# LEDMotherboard.net
KiCad netlist of a schematic drawn in EAGLE
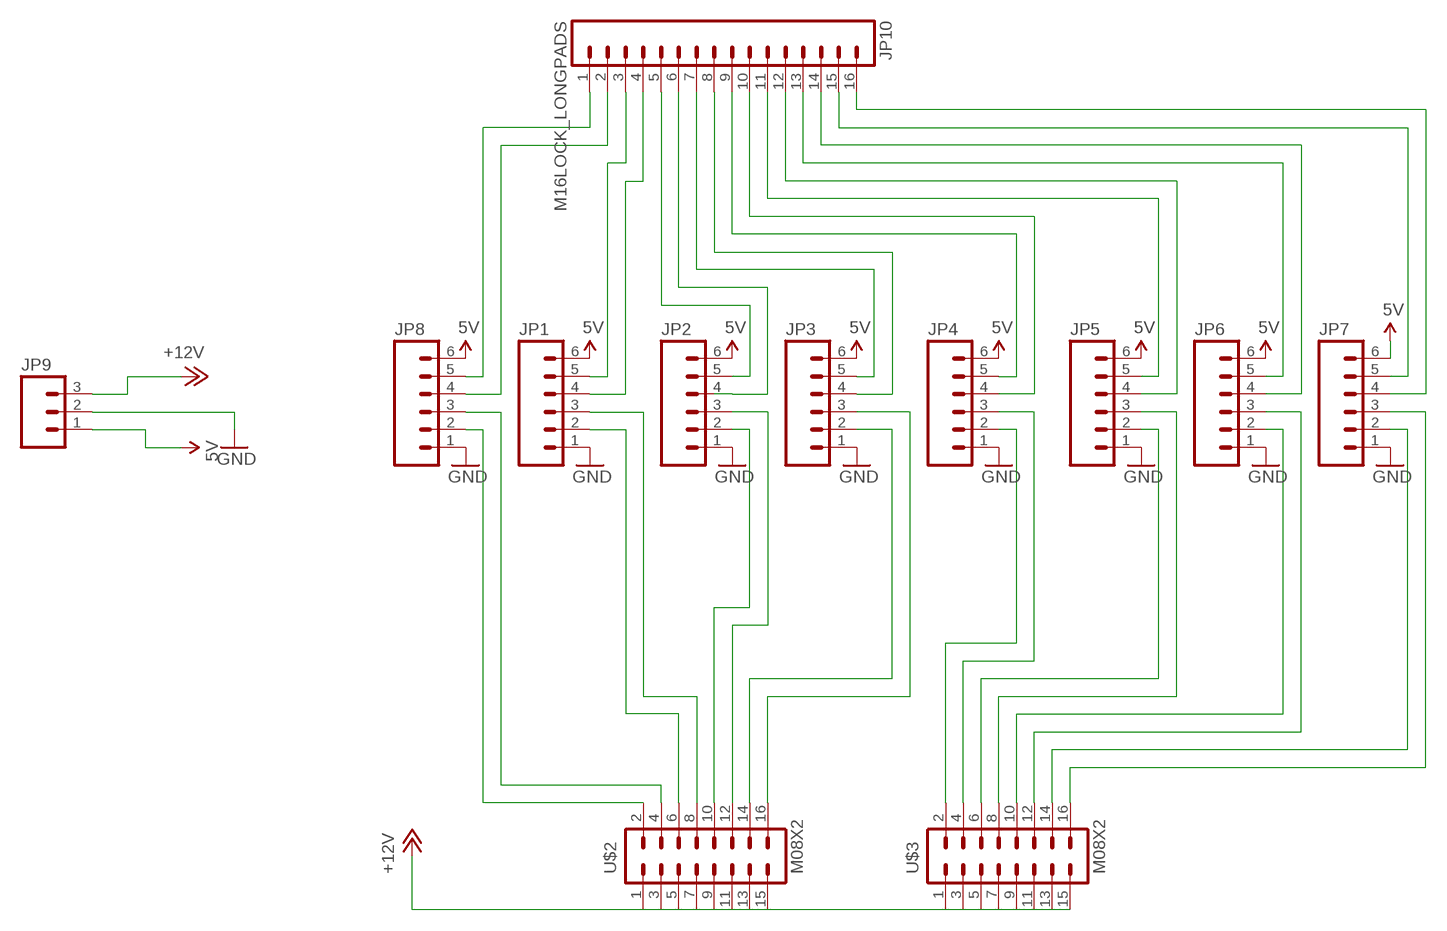
[diagram p0: schematic, sheet 1]

(export (version "E")
  (design (tool "Eeschema 10.0.6"))
  (components
    (comp (ref "JP1")
      (value "M06LOCK_LONGPADS")
      (footprint "eagle-import:1X06_LOCK_LONGPADS")
      (libsource (lib "eagle-import") (part "M06LOCK_LONGPADS"))
    )
    (comp (ref "JP2")
      (value "M06LOCK_LONGPADS")
      (footprint "eagle-import:1X06_LOCK_LONGPADS")
      (libsource (lib "eagle-import") (part "M06LOCK_LONGPADS"))
    )
    (comp (ref "JP3")
      (value "M06LOCK_LONGPADS")
      (footprint "eagle-import:1X06_LOCK_LONGPADS")
      (libsource (lib "eagle-import") (part "M06LOCK_LONGPADS"))
    )
    (comp (ref "JP4")
      (value "M06LOCK_LONGPADS")
      (footprint "eagle-import:1X06_LOCK_LONGPADS")
      (libsource (lib "eagle-import") (part "M06LOCK_LONGPADS"))
    )
    (comp (ref "JP5")
      (value "M06LOCK_LONGPADS")
      (footprint "eagle-import:1X06_LOCK_LONGPADS")
      (libsource (lib "eagle-import") (part "M06LOCK_LONGPADS"))
    )
    (comp (ref "JP6")
      (value "M06LOCK_LONGPADS")
      (footprint "eagle-import:1X06_LOCK_LONGPADS")
      (libsource (lib "eagle-import") (part "M06LOCK_LONGPADS"))
    )
    (comp (ref "JP7")
      (value "M06LOCK_LONGPADS")
      (footprint "eagle-import:1X06_LOCK_LONGPADS")
      (libsource (lib "eagle-import") (part "M06LOCK_LONGPADS"))
    )
    (comp (ref "JP8")
      (value "M06LOCK_LONGPADS")
      (footprint "eagle-import:1X06_LOCK_LONGPADS")
      (libsource (lib "eagle-import") (part "M06LOCK_LONGPADS"))
    )
    (comp (ref "JP9")
      (value "M03-SCREW-5MM")
      (footprint "eagle-import:SCREWTERMINAL-5MM-3")
      (libsource (lib "eagle-import") (part "M03-SCREW-5MM"))
    )
    (comp (ref "JP10")
      (value "M16LOCK_LONGPADS")
      (footprint "eagle-import:1X16_LOCK_LONGPADS")
      (libsource (lib "eagle-import") (part "M16LOCK_LONGPADS"))
    )
    (comp (ref "U$2")
      (value "M08X2")
      (footprint "eagle-import:2X8")
      (libsource (lib "eagle-import") (part "M08X2"))
    )
    (comp (ref "U$3")
      (value "M08X2")
      (footprint "eagle-import:2X8")
      (libsource (lib "eagle-import") (part "M08X2"))
    )
  )
  (nets
    (net (code "1") (name "+12V") (class "Default")
      (node (ref "JP9") (pin "3") (pinfunction "3_3") (pintype "passive"))
      (node (ref "U$2") (pin "1") (pinfunction "1_1") (pintype "passive"))
      (node (ref "U$2") (pin "11") (pinfunction "11_11") (pintype "passive"))
      (node (ref "U$2") (pin "13") (pinfunction "13_13") (pintype "passive"))
      (node (ref "U$2") (pin "15") (pinfunction "15_15") (pintype "passive"))
      (node (ref "U$2") (pin "3") (pinfunction "3_3") (pintype "passive"))
      (node (ref "U$2") (pin "5") (pinfunction "5_5") (pintype "passive"))
      (node (ref "U$2") (pin "7") (pinfunction "7_7") (pintype "passive"))
      (node (ref "U$2") (pin "9") (pinfunction "9_9") (pintype "passive"))
      (node (ref "U$3") (pin "1") (pinfunction "1_1") (pintype "passive"))
      (node (ref "U$3") (pin "11") (pinfunction "11_11") (pintype "passive"))
      (node (ref "U$3") (pin "13") (pinfunction "13_13") (pintype "passive"))
      (node (ref "U$3") (pin "15") (pinfunction "15_15") (pintype "passive"))
      (node (ref "U$3") (pin "3") (pinfunction "3_3") (pintype "passive"))
      (node (ref "U$3") (pin "5") (pinfunction "5_5") (pintype "passive"))
      (node (ref "U$3") (pin "7") (pinfunction "7_7") (pintype "passive"))
      (node (ref "U$3") (pin "9") (pinfunction "9_9") (pintype "passive"))
    )
    (net (code "2") (name "5V") (class "Default")
      (node (ref "JP1") (pin "6") (pinfunction "6_6") (pintype "passive"))
      (node (ref "JP2") (pin "6") (pinfunction "6_6") (pintype "passive"))
      (node (ref "JP3") (pin "6") (pinfunction "6_6") (pintype "passive"))
      (node (ref "JP4") (pin "6") (pinfunction "6_6") (pintype "passive"))
      (node (ref "JP5") (pin "6") (pinfunction "6_6") (pintype "passive"))
      (node (ref "JP6") (pin "6") (pinfunction "6_6") (pintype "passive"))
      (node (ref "JP7") (pin "6") (pinfunction "6_6") (pintype "passive"))
      (node (ref "JP8") (pin "6") (pinfunction "6_6") (pintype "passive"))
      (node (ref "JP9") (pin "1") (pinfunction "1_1") (pintype "passive"))
    )
    (net (code "3") (name "GND") (class "Default")
      (node (ref "JP1") (pin "1") (pinfunction "1_1") (pintype "passive"))
      (node (ref "JP2") (pin "1") (pinfunction "1_1") (pintype "passive"))
      (node (ref "JP3") (pin "1") (pinfunction "1_1") (pintype "passive"))
      (node (ref "JP4") (pin "1") (pinfunction "1_1") (pintype "passive"))
      (node (ref "JP5") (pin "1") (pinfunction "1_1") (pintype "passive"))
      (node (ref "JP6") (pin "1") (pinfunction "1_1") (pintype "passive"))
      (node (ref "JP7") (pin "1") (pinfunction "1_1") (pintype "passive"))
      (node (ref "JP8") (pin "1") (pinfunction "1_1") (pintype "passive"))
      (node (ref "JP9") (pin "2") (pinfunction "2_2") (pintype "passive"))
    )
    (net (code "4") (name "Net-(JP1-Pad2)") (class "Default")
      (node (ref "JP1") (pin "2") (pinfunction "2_2") (pintype "passive"))
      (node (ref "U$2") (pin "6") (pinfunction "6_6") (pintype "passive"))
    )
    (net (code "5") (name "Net-(JP1-Pad3)") (class "Default")
      (node (ref "JP1") (pin "3") (pinfunction "3_3") (pintype "passive"))
      (node (ref "U$2") (pin "8") (pinfunction "8_8") (pintype "passive"))
    )
    (net (code "6") (name "Net-(JP1-Pad4)") (class "Default")
      (node (ref "JP1") (pin "4") (pinfunction "4_4") (pintype "passive"))
      (node (ref "JP10") (pin "4") (pinfunction "4_4") (pintype "passive"))
    )
    (net (code "7") (name "Net-(JP1-Pad5)") (class "Default")
      (node (ref "JP1") (pin "5") (pinfunction "5_5") (pintype "passive"))
      (node (ref "JP10") (pin "3") (pinfunction "3_3") (pintype "passive"))
    )
    (net (code "8") (name "Net-(JP2-Pad2)") (class "Default")
      (node (ref "JP2") (pin "2") (pinfunction "2_2") (pintype "passive"))
      (node (ref "U$2") (pin "10") (pinfunction "10_10") (pintype "passive"))
    )
    (net (code "9") (name "Net-(JP2-Pad3)") (class "Default")
      (node (ref "JP2") (pin "3") (pinfunction "3_3") (pintype "passive"))
      (node (ref "U$2") (pin "12") (pinfunction "12_12") (pintype "passive"))
    )
    (net (code "10") (name "Net-(JP3-Pad2)") (class "Default")
      (node (ref "JP3") (pin "2") (pinfunction "2_2") (pintype "passive"))
      (node (ref "U$2") (pin "14") (pinfunction "14_14") (pintype "passive"))
    )
    (net (code "11") (name "Net-(JP3-Pad3)") (class "Default")
      (node (ref "JP3") (pin "3") (pinfunction "3_3") (pintype "passive"))
      (node (ref "U$2") (pin "16") (pinfunction "16_16") (pintype "passive"))
    )
    (net (code "12") (name "Net-(JP4-Pad2)") (class "Default")
      (node (ref "JP4") (pin "2") (pinfunction "2_2") (pintype "passive"))
      (node (ref "U$3") (pin "2") (pinfunction "2_2") (pintype "passive"))
    )
    (net (code "13") (name "Net-(JP4-Pad3)") (class "Default")
      (node (ref "JP4") (pin "3") (pinfunction "3_3") (pintype "passive"))
      (node (ref "U$3") (pin "4") (pinfunction "4_4") (pintype "passive"))
    )
    (net (code "14") (name "Net-(JP5-Pad2)") (class "Default")
      (node (ref "JP5") (pin "2") (pinfunction "2_2") (pintype "passive"))
      (node (ref "U$3") (pin "6") (pinfunction "6_6") (pintype "passive"))
    )
    (net (code "15") (name "Net-(JP5-Pad3)") (class "Default")
      (node (ref "JP5") (pin "3") (pinfunction "3_3") (pintype "passive"))
      (node (ref "U$3") (pin "8") (pinfunction "8_8") (pintype "passive"))
    )
    (net (code "16") (name "Net-(JP6-Pad2)") (class "Default")
      (node (ref "JP6") (pin "2") (pinfunction "2_2") (pintype "passive"))
      (node (ref "U$3") (pin "10") (pinfunction "10_10") (pintype "passive"))
    )
    (net (code "17") (name "Net-(JP6-Pad3)") (class "Default")
      (node (ref "JP6") (pin "3") (pinfunction "3_3") (pintype "passive"))
      (node (ref "U$3") (pin "12") (pinfunction "12_12") (pintype "passive"))
    )
    (net (code "18") (name "Net-(JP7-Pad2)") (class "Default")
      (node (ref "JP7") (pin "2") (pinfunction "2_2") (pintype "passive"))
      (node (ref "U$3") (pin "14") (pinfunction "14_14") (pintype "passive"))
    )
    (net (code "19") (name "Net-(JP7-Pad3)") (class "Default")
      (node (ref "JP7") (pin "3") (pinfunction "3_3") (pintype "passive"))
      (node (ref "U$3") (pin "16") (pinfunction "16_16") (pintype "passive"))
    )
    (net (code "20") (name "Net-(JP8-Pad2)") (class "Default")
      (node (ref "JP8") (pin "2") (pinfunction "2_2") (pintype "passive"))
      (node (ref "U$2") (pin "2") (pinfunction "2_2") (pintype "passive"))
    )
    (net (code "21") (name "Net-(JP8-Pad3)") (class "Default")
      (node (ref "JP8") (pin "3") (pinfunction "3_3") (pintype "passive"))
      (node (ref "U$2") (pin "4") (pinfunction "4_4") (pintype "passive"))
    )
    (net (code "22") (name "Net-(JP10-Pad1)") (class "Default")
      (node (ref "JP10") (pin "1") (pinfunction "1_1") (pintype "passive"))
      (node (ref "JP8") (pin "5") (pinfunction "5_5") (pintype "passive"))
    )
    (net (code "23") (name "Net-(JP10-Pad2)") (class "Default")
      (node (ref "JP10") (pin "2") (pinfunction "2_2") (pintype "passive"))
      (node (ref "JP8") (pin "4") (pinfunction "4_4") (pintype "passive"))
    )
    (net (code "24") (name "Net-(JP10-Pad5)") (class "Default")
      (node (ref "JP10") (pin "5") (pinfunction "5_5") (pintype "passive"))
      (node (ref "JP2") (pin "5") (pinfunction "5_5") (pintype "passive"))
    )
    (net (code "25") (name "Net-(JP10-Pad6)") (class "Default")
      (node (ref "JP10") (pin "6") (pinfunction "6_6") (pintype "passive"))
      (node (ref "JP2") (pin "4") (pinfunction "4_4") (pintype "passive"))
    )
    (net (code "26") (name "Net-(JP10-Pad7)") (class "Default")
      (node (ref "JP10") (pin "7") (pinfunction "7_7") (pintype "passive"))
      (node (ref "JP3") (pin "5") (pinfunction "5_5") (pintype "passive"))
    )
    (net (code "27") (name "Net-(JP10-Pad8)") (class "Default")
      (node (ref "JP10") (pin "8") (pinfunction "8_8") (pintype "passive"))
      (node (ref "JP3") (pin "4") (pinfunction "4_4") (pintype "passive"))
    )
    (net (code "28") (name "Net-(JP10-Pad9)") (class "Default")
      (node (ref "JP10") (pin "9") (pinfunction "9_9") (pintype "passive"))
      (node (ref "JP4") (pin "5") (pinfunction "5_5") (pintype "passive"))
    )
    (net (code "29") (name "Net-(JP10-Pad10)") (class "Default")
      (node (ref "JP10") (pin "10") (pinfunction "10_10") (pintype "passive"))
      (node (ref "JP4") (pin "4") (pinfunction "4_4") (pintype "passive"))
    )
    (net (code "30") (name "Net-(JP10-Pad11)") (class "Default")
      (node (ref "JP10") (pin "11") (pinfunction "11_11") (pintype "passive"))
      (node (ref "JP5") (pin "5") (pinfunction "5_5") (pintype "passive"))
    )
    (net (code "31") (name "Net-(JP10-Pad12)") (class "Default")
      (node (ref "JP10") (pin "12") (pinfunction "12_12") (pintype "passive"))
      (node (ref "JP5") (pin "4") (pinfunction "4_4") (pintype "passive"))
    )
    (net (code "32") (name "Net-(JP10-Pad13)") (class "Default")
      (node (ref "JP10") (pin "13") (pinfunction "13_13") (pintype "passive"))
      (node (ref "JP6") (pin "5") (pinfunction "5_5") (pintype "passive"))
    )
    (net (code "33") (name "Net-(JP10-Pad14)") (class "Default")
      (node (ref "JP10") (pin "14") (pinfunction "14_14") (pintype "passive"))
      (node (ref "JP6") (pin "4") (pinfunction "4_4") (pintype "passive"))
    )
    (net (code "34") (name "Net-(JP10-Pad15)") (class "Default")
      (node (ref "JP10") (pin "15") (pinfunction "15_15") (pintype "passive"))
      (node (ref "JP7") (pin "5") (pinfunction "5_5") (pintype "passive"))
    )
    (net (code "35") (name "Net-(JP10-Pad16)") (class "Default")
      (node (ref "JP10") (pin "16") (pinfunction "16_16") (pintype "passive"))
      (node (ref "JP7") (pin "4") (pinfunction "4_4") (pintype "passive"))
    )
  )
)
